# main_controller.net
KiCad netlist of a schematic drawn in EAGLE
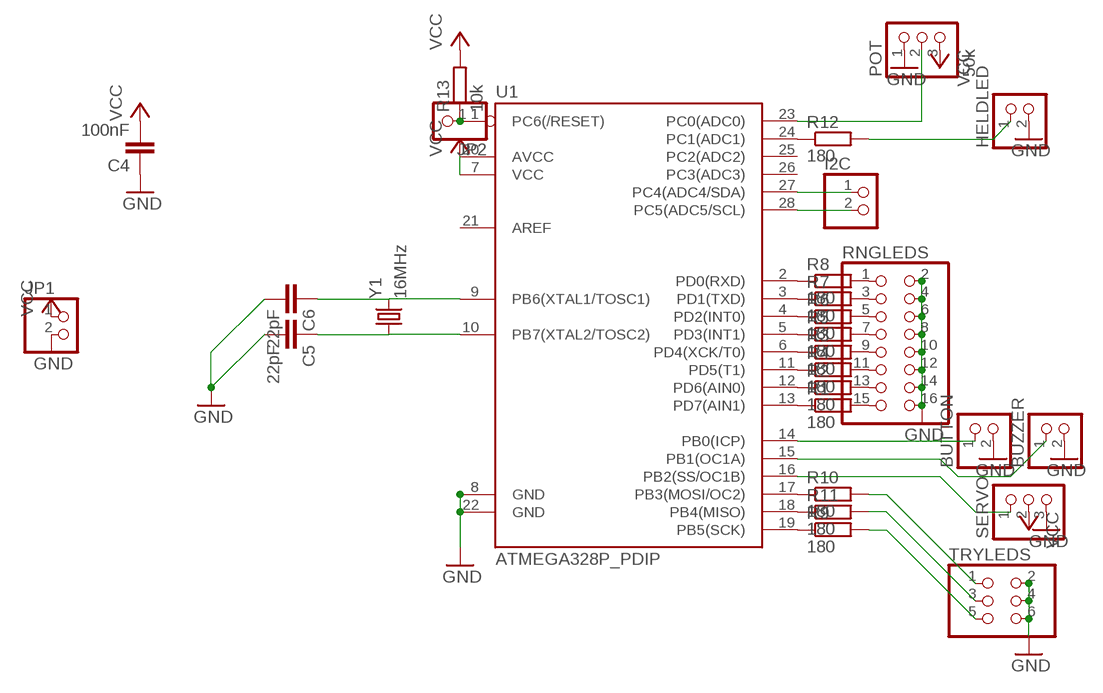
[diagram p0: schematic, sheet 1]

(export (version "E")
  (design (tool "Eeschema 10.0.6"))
  (components
    (comp (ref "BUTTON")
      (value "PINHD-1X2")
      (footprint "eagle-import:1X02")
      (libsource (lib "eagle-import") (part "PINHD-1X2"))
    )
    (comp (ref "BUZZER")
      (value "PINHD-1X2")
      (footprint "eagle-import:1X02")
      (libsource (lib "eagle-import") (part "PINHD-1X2"))
    )
    (comp (ref "C4")
      (value "100nF")
      (footprint "eagle-import:C050-025X075")
      (libsource (lib "eagle-import") (part "C-EU050-025X075"))
    )
    (comp (ref "C5")
      (value "22pF")
      (footprint "eagle-import:C050-025X075")
      (libsource (lib "eagle-import") (part "C-EU050-025X075"))
    )
    (comp (ref "C6")
      (value "22pF")
      (footprint "eagle-import:C050-025X075")
      (libsource (lib "eagle-import") (part "C-EU050-025X075"))
    )
    (comp (ref "HELDLED")
      (value "PINHD-1X2")
      (footprint "eagle-import:1X02")
      (libsource (lib "eagle-import") (part "PINHD-1X2"))
    )
    (comp (ref "I2C")
      (value "PINHD-1X2")
      (footprint "eagle-import:1X02")
      (libsource (lib "eagle-import") (part "PINHD-1X2"))
    )
    (comp (ref "JP1")
      (value "PINHD-1X2")
      (footprint "eagle-import:1X02")
      (libsource (lib "eagle-import") (part "PINHD-1X2"))
    )
    (comp (ref "JP2")
      (value "PINHD-1X1")
      (footprint "eagle-import:1X01")
      (libsource (lib "eagle-import") (part "PINHD-1X1"))
    )
    (comp (ref "POT")
      (value "50k")
      (footprint "eagle-import:1X03")
      (libsource (lib "eagle-import") (part "PINHD-1X3"))
    )
    (comp (ref "R1")
      (value "180")
      (footprint "eagle-import:0207_7")
      (libsource (lib "eagle-import") (part "R-EU_0207/7"))
    )
    (comp (ref "R2")
      (value "180")
      (footprint "eagle-import:0207_7")
      (libsource (lib "eagle-import") (part "R-EU_0207/7"))
    )
    (comp (ref "R3")
      (value "180")
      (footprint "eagle-import:0207_7")
      (libsource (lib "eagle-import") (part "R-EU_0207/7"))
    )
    (comp (ref "R4")
      (value "180")
      (footprint "eagle-import:0207_7")
      (libsource (lib "eagle-import") (part "R-EU_0207/7"))
    )
    (comp (ref "R5")
      (value "180")
      (footprint "eagle-import:0207_7")
      (libsource (lib "eagle-import") (part "R-EU_0207/7"))
    )
    (comp (ref "R6")
      (value "180")
      (footprint "eagle-import:0207_7")
      (libsource (lib "eagle-import") (part "R-EU_0207/7"))
    )
    (comp (ref "R7")
      (value "180")
      (footprint "eagle-import:0207_7")
      (libsource (lib "eagle-import") (part "R-EU_0207/7"))
    )
    (comp (ref "R8")
      (value "180")
      (footprint "eagle-import:0207_7")
      (libsource (lib "eagle-import") (part "R-EU_0207/7"))
    )
    (comp (ref "R9")
      (value "180")
      (footprint "eagle-import:0207_7")
      (libsource (lib "eagle-import") (part "R-EU_0207/7"))
    )
    (comp (ref "R10")
      (value "180")
      (footprint "eagle-import:0207_7")
      (libsource (lib "eagle-import") (part "R-EU_0207/7"))
    )
    (comp (ref "R11")
      (value "180")
      (footprint "eagle-import:0207_7")
      (libsource (lib "eagle-import") (part "R-EU_0207/7"))
    )
    (comp (ref "R12")
      (value "180")
      (footprint "eagle-import:0207_7")
      (libsource (lib "eagle-import") (part "R-EU_0207/7"))
    )
    (comp (ref "R13")
      (value "10k")
      (footprint "eagle-import:0207_7")
      (libsource (lib "eagle-import") (part "R-EU_0207/7"))
    )
    (comp (ref "RNGLEDS")
      (value "PINHD-2X8")
      (footprint "eagle-import:2X08")
      (libsource (lib "eagle-import") (part "PINHD-2X8"))
    )
    (comp (ref "SERVO")
      (value "PINHD-1X3")
      (footprint "eagle-import:1X03")
      (libsource (lib "eagle-import") (part "PINHD-1X3"))
    )
    (comp (ref "TRYLEDS")
      (value "PINHD-2X3")
      (footprint "eagle-import:2X03")
      (libsource (lib "eagle-import") (part "PINHD-2X3"))
    )
    (comp (ref "U1")
      (value "ATMEGA328P_PDIP")
      (footprint "eagle-import:DIL28-3")
      (libsource (lib "eagle-import") (part "ATMEGA328P_PDIP"))
    )
    (comp (ref "Y1")
      (value "16MHz")
      (footprint "eagle-import:HC49US")
      (libsource (lib "eagle-import") (part "CRYSTALHC49US"))
    )
  )
  (nets
    (net (code "1") (name "GND") (class "Default")
      (node (ref "BUTTON") (pin "2") (pinfunction "2_2") (pintype "passive"))
      (node (ref "BUZZER") (pin "2") (pinfunction "2_2") (pintype "passive"))
      (node (ref "C4") (pin "1") (pinfunction "1_1") (pintype "passive"))
      (node (ref "C5") (pin "2") (pinfunction "2_2") (pintype "passive"))
      (node (ref "C6") (pin "2") (pinfunction "2_2") (pintype "passive"))
      (node (ref "HELDLED") (pin "2") (pinfunction "2_2") (pintype "passive"))
      (node (ref "JP1") (pin "2") (pinfunction "2_2") (pintype "passive"))
      (node (ref "POT") (pin "1") (pinfunction "1_1") (pintype "passive"))
      (node (ref "RNGLEDS") (pin "10") (pinfunction "10_10") (pintype "passive"))
      (node (ref "RNGLEDS") (pin "12") (pinfunction "12_12") (pintype "passive"))
      (node (ref "RNGLEDS") (pin "14") (pinfunction "14_14") (pintype "passive"))
      (node (ref "RNGLEDS") (pin "16") (pinfunction "16_16") (pintype "passive"))
      (node (ref "RNGLEDS") (pin "2") (pinfunction "2_2") (pintype "passive"))
      (node (ref "RNGLEDS") (pin "4") (pinfunction "4_4") (pintype "passive"))
      (node (ref "RNGLEDS") (pin "6") (pinfunction "6_6") (pintype "passive"))
      (node (ref "RNGLEDS") (pin "8") (pinfunction "8_8") (pintype "passive"))
      (node (ref "SERVO") (pin "3") (pinfunction "3_3") (pintype "passive"))
      (node (ref "TRYLEDS") (pin "2") (pinfunction "2_2") (pintype "passive"))
      (node (ref "TRYLEDS") (pin "4") (pinfunction "4_4") (pintype "passive"))
      (node (ref "TRYLEDS") (pin "6") (pinfunction "6_6") (pintype "passive"))
      (node (ref "U1") (pin "22") (pinfunction "GND_22") (pintype "bidirectional"))
      (node (ref "U1") (pin "8") (pinfunction "GND_8") (pintype "bidirectional"))
    )
    (net (code "2") (name "Net-(HELDLED-Pad1)") (class "Default")
      (node (ref "HELDLED") (pin "1") (pinfunction "1_1") (pintype "passive"))
      (node (ref "R12") (pin "2") (pinfunction "2_2") (pintype "passive"))
    )
    (net (code "3") (name "Net-(R1-Pad2)") (class "Default")
      (node (ref "R1") (pin "2") (pinfunction "2_2") (pintype "passive"))
      (node (ref "RNGLEDS") (pin "15") (pinfunction "15_15") (pintype "passive"))
    )
    (net (code "4") (name "Net-(R2-Pad2)") (class "Default")
      (node (ref "R2") (pin "2") (pinfunction "2_2") (pintype "passive"))
      (node (ref "RNGLEDS") (pin "13") (pinfunction "13_13") (pintype "passive"))
    )
    (net (code "5") (name "Net-(R3-Pad2)") (class "Default")
      (node (ref "R3") (pin "2") (pinfunction "2_2") (pintype "passive"))
      (node (ref "RNGLEDS") (pin "9") (pinfunction "9_9") (pintype "passive"))
    )
    (net (code "6") (name "Net-(R4-Pad2)") (class "Default")
      (node (ref "R4") (pin "2") (pinfunction "2_2") (pintype "passive"))
      (node (ref "RNGLEDS") (pin "11") (pinfunction "11_11") (pintype "passive"))
    )
    (net (code "7") (name "Net-(R5-Pad2)") (class "Default")
      (node (ref "R5") (pin "2") (pinfunction "2_2") (pintype "passive"))
      (node (ref "RNGLEDS") (pin "7") (pinfunction "7_7") (pintype "passive"))
    )
    (net (code "8") (name "Net-(R6-Pad2)") (class "Default")
      (node (ref "R6") (pin "2") (pinfunction "2_2") (pintype "passive"))
      (node (ref "RNGLEDS") (pin "5") (pinfunction "5_5") (pintype "passive"))
    )
    (net (code "9") (name "Net-(R7-Pad2)") (class "Default")
      (node (ref "R7") (pin "2") (pinfunction "2_2") (pintype "passive"))
      (node (ref "RNGLEDS") (pin "3") (pinfunction "3_3") (pintype "passive"))
    )
    (net (code "10") (name "Net-(R8-Pad2)") (class "Default")
      (node (ref "R8") (pin "2") (pinfunction "2_2") (pintype "passive"))
      (node (ref "RNGLEDS") (pin "1") (pinfunction "1_1") (pintype "passive"))
    )
    (net (code "11") (name "Net-(R9-Pad2)") (class "Default")
      (node (ref "R9") (pin "2") (pinfunction "2_2") (pintype "passive"))
      (node (ref "TRYLEDS") (pin "5") (pinfunction "5_5") (pintype "passive"))
    )
    (net (code "12") (name "Net-(R10-Pad2)") (class "Default")
      (node (ref "R10") (pin "2") (pinfunction "2_2") (pintype "passive"))
      (node (ref "TRYLEDS") (pin "1") (pinfunction "1_1") (pintype "passive"))
    )
    (net (code "13") (name "Net-(R11-Pad2)") (class "Default")
      (node (ref "R11") (pin "2") (pinfunction "2_2") (pintype "passive"))
      (node (ref "TRYLEDS") (pin "3") (pinfunction "3_3") (pintype "passive"))
    )
    (net (code "14") (name "Net-(U1-PB0(ICP))") (class "Default")
      (node (ref "BUTTON") (pin "1") (pinfunction "1_1") (pintype "passive"))
      (node (ref "U1") (pin "14") (pinfunction "PB0(ICP)_14") (pintype "bidirectional"))
    )
    (net (code "15") (name "Net-(U1-PB1(OC1A))") (class "Default")
      (node (ref "BUZZER") (pin "1") (pinfunction "1_1") (pintype "passive"))
      (node (ref "U1") (pin "15") (pinfunction "PB1(OC1A)_15") (pintype "bidirectional"))
    )
    (net (code "16") (name "Net-(U1-PB2(SS{slash}OC1B))") (class "Default")
      (node (ref "SERVO") (pin "1") (pinfunction "1_1") (pintype "passive"))
      (node (ref "U1") (pin "16") (pinfunction "PB2(SS/OC1B)_16") (pintype "bidirectional"))
    )
    (net (code "17") (name "Net-(U1-PB3(MOSI{slash}OC2))") (class "Default")
      (node (ref "R10") (pin "1") (pinfunction "1_1") (pintype "passive"))
      (node (ref "U1") (pin "17") (pinfunction "PB3(MOSI/OC2)_17") (pintype "bidirectional"))
    )
    (net (code "18") (name "Net-(U1-PB4(MISO))") (class "Default")
      (node (ref "R11") (pin "1") (pinfunction "1_1") (pintype "passive"))
      (node (ref "U1") (pin "18") (pinfunction "PB4(MISO)_18") (pintype "bidirectional"))
    )
    (net (code "19") (name "Net-(U1-PB5(SCK))") (class "Default")
      (node (ref "R9") (pin "1") (pinfunction "1_1") (pintype "passive"))
      (node (ref "U1") (pin "19") (pinfunction "PB5(SCK)_19") (pintype "bidirectional"))
    )
    (net (code "20") (name "Net-(U1-PB6(XTAL1{slash}TOSC1))") (class "Default")
      (node (ref "C6") (pin "1") (pinfunction "1_1") (pintype "passive"))
      (node (ref "U1") (pin "9") (pinfunction "PB6(XTAL1/TOSC1)_9") (pintype "bidirectional"))
      (node (ref "Y1") (pin "2") (pinfunction "2_2") (pintype "passive"))
    )
    (net (code "21") (name "Net-(U1-PB7(XTAL2{slash}TOSC2))") (class "Default")
      (node (ref "C5") (pin "1") (pinfunction "1_1") (pintype "passive"))
      (node (ref "U1") (pin "10") (pinfunction "PB7(XTAL2/TOSC2)_10") (pintype "bidirectional"))
      (node (ref "Y1") (pin "1") (pinfunction "1_1") (pintype "passive"))
    )
    (net (code "22") (name "Net-(U1-PC0(ADC0))") (class "Default")
      (node (ref "POT") (pin "2") (pinfunction "2_2") (pintype "passive"))
      (node (ref "U1") (pin "23") (pinfunction "PC0(ADC0)_23") (pintype "bidirectional"))
    )
    (net (code "23") (name "Net-(U1-PC1(ADC1))") (class "Default")
      (node (ref "R12") (pin "1") (pinfunction "1_1") (pintype "passive"))
      (node (ref "U1") (pin "24") (pinfunction "PC1(ADC1)_24") (pintype "bidirectional"))
    )
    (net (code "24") (name "Net-(U1-PC4(ADC4{slash}SDA))") (class "Default")
      (node (ref "I2C") (pin "1") (pinfunction "1_1") (pintype "passive"))
      (node (ref "U1") (pin "27") (pinfunction "PC4(ADC4/SDA)_27") (pintype "bidirectional"))
    )
    (net (code "25") (name "Net-(U1-PC5(ADC5{slash}SCL))") (class "Default")
      (node (ref "I2C") (pin "2") (pinfunction "2_2") (pintype "passive"))
      (node (ref "U1") (pin "28") (pinfunction "PC5(ADC5/SCL)_28") (pintype "bidirectional"))
    )
    (net (code "26") (name "Net-(U1-PC6({slash}RESET))") (class "Default")
      (node (ref "JP2") (pin "1") (pinfunction "1_1") (pintype "passive"))
      (node (ref "R13") (pin "1") (pinfunction "1_1") (pintype "passive"))
      (node (ref "U1") (pin "1") (pinfunction "PC6(/RESET)_1") (pintype "bidirectional"))
    )
    (net (code "27") (name "Net-(U1-PD0(RXD))") (class "Default")
      (node (ref "R8") (pin "1") (pinfunction "1_1") (pintype "passive"))
      (node (ref "U1") (pin "2") (pinfunction "PD0(RXD)_2") (pintype "bidirectional"))
    )
    (net (code "28") (name "Net-(U1-PD1(TXD))") (class "Default")
      (node (ref "R7") (pin "1") (pinfunction "1_1") (pintype "passive"))
      (node (ref "U1") (pin "3") (pinfunction "PD1(TXD)_3") (pintype "bidirectional"))
    )
    (net (code "29") (name "Net-(U1-PD2(INT0))") (class "Default")
      (node (ref "R6") (pin "1") (pinfunction "1_1") (pintype "passive"))
      (node (ref "U1") (pin "4") (pinfunction "PD2(INT0)_4") (pintype "bidirectional"))
    )
    (net (code "30") (name "Net-(U1-PD3(INT1))") (class "Default")
      (node (ref "R5") (pin "1") (pinfunction "1_1") (pintype "passive"))
      (node (ref "U1") (pin "5") (pinfunction "PD3(INT1)_5") (pintype "bidirectional"))
    )
    (net (code "31") (name "Net-(U1-PD4(XCK{slash}T0))") (class "Default")
      (node (ref "R3") (pin "1") (pinfunction "1_1") (pintype "passive"))
      (node (ref "U1") (pin "6") (pinfunction "PD4(XCK/T0)_6") (pintype "bidirectional"))
    )
    (net (code "32") (name "Net-(U1-PD5(T1))") (class "Default")
      (node (ref "R4") (pin "1") (pinfunction "1_1") (pintype "passive"))
      (node (ref "U1") (pin "11") (pinfunction "PD5(T1)_11") (pintype "bidirectional"))
    )
    (net (code "33") (name "Net-(U1-PD6(AIN0))") (class "Default")
      (node (ref "R2") (pin "1") (pinfunction "1_1") (pintype "passive"))
      (node (ref "U1") (pin "12") (pinfunction "PD6(AIN0)_12") (pintype "bidirectional"))
    )
    (net (code "34") (name "Net-(U1-PD7(AIN1))") (class "Default")
      (node (ref "R1") (pin "1") (pinfunction "1_1") (pintype "passive"))
      (node (ref "U1") (pin "13") (pinfunction "PD7(AIN1)_13") (pintype "bidirectional"))
    )
    (net (code "35") (name "VCC") (class "Default")
      (node (ref "C4") (pin "2") (pinfunction "2_2") (pintype "passive"))
      (node (ref "JP1") (pin "1") (pinfunction "1_1") (pintype "passive"))
      (node (ref "POT") (pin "3") (pinfunction "3_3") (pintype "passive"))
      (node (ref "R13") (pin "2") (pinfunction "2_2") (pintype "passive"))
      (node (ref "SERVO") (pin "2") (pinfunction "2_2") (pintype "passive"))
      (node (ref "U1") (pin "20") (pinfunction "AVCC_20") (pintype "bidirectional"))
      (node (ref "U1") (pin "7") (pinfunction "VCC_7") (pintype "bidirectional"))
    )
    (net (code "36") (name "unconnected-(U1-AREF-Pad21)") (class "Default")
      (node (ref "U1") (pin "21") (pinfunction "AREF_21") (pintype "bidirectional"))
    )
    (net (code "37") (name "unconnected-(U1-PC2(ADC2)-Pad25)") (class "Default")
      (node (ref "U1") (pin "25") (pinfunction "PC2(ADC2)_25") (pintype "bidirectional"))
    )
    (net (code "38") (name "unconnected-(U1-PC3(ADC3)-Pad26)") (class "Default")
      (node (ref "U1") (pin "26") (pinfunction "PC3(ADC3)_26") (pintype "bidirectional"))
    )
  )
)
